# Microcontr_leur_et_capteur_temp.net
KiCad netlist of a schematic drawn in Altium Designer
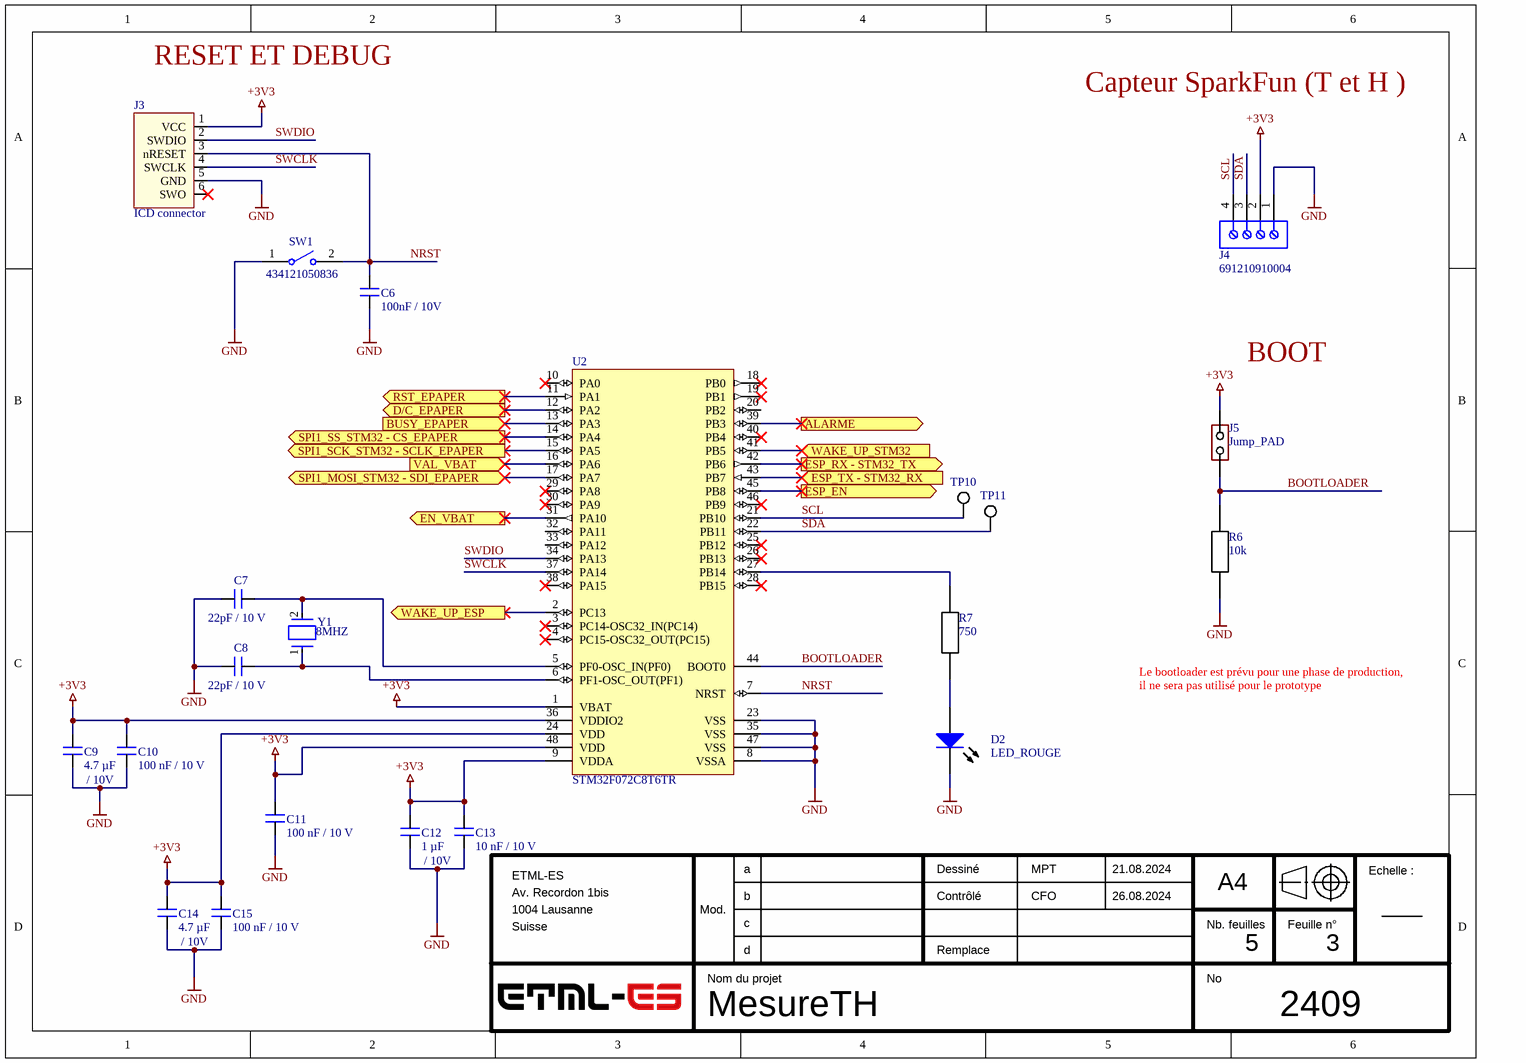
[diagram p0: Microcontrôleur et capteur temp.SchDoc]

(export (version "E")
  (design (tool "Eeschema 10.0.6"))
  (components
    (comp (ref "C6")
      (value "100nF / 10V")
      (footprint "WCAP-CSGP_0805_L2W1.25H0.8_Wave")
      (libsource (lib "Composants_Projet_2409") (part "CAPA"))
    )
    (comp (ref "C7")
      (value "22pF / 10 V")
      (footprint "WCAP-CSGP_0805_L2W1.25H0.8_Wave")
      (libsource (lib "Composants_Projet_2409") (part "CAPA"))
    )
    (comp (ref "C8")
      (value "22pF / 10 V")
      (footprint "WCAP-CSGP_0805_L2W1.25H0.8_Wave")
      (libsource (lib "Composants_Projet_2409") (part "CAPA"))
    )
    (comp (ref "C9")
      (value "4.7 µF")
      (footprint "WCAP-CSGP_0805_L2W1.25H0.8_Wave")
      (libsource (lib "Composants_Projet_2409") (part "CAPA"))
    )
    (comp (ref "C10")
      (value "100 nF / 10 V")
      (footprint "WCAP-CSGP_0805_L2W1.25H0.8_Wave")
      (libsource (lib "Composants_Projet_2409") (part "CAPA"))
    )
    (comp (ref "C11")
      (value "100 nF / 10 V")
      (footprint "WCAP-CSGP_0805_L2W1.25H0.8_Wave")
      (libsource (lib "Composants_Projet_2409") (part "CAPA"))
    )
    (comp (ref "C12")
      (value "1 µF")
      (footprint "WCAP-CSGP_0805_L2W1.25H0.8_Wave")
      (libsource (lib "Composants_Projet_2409") (part "CAPA"))
    )
    (comp (ref "C13")
      (value "10 nF / 10 V")
      (footprint "WCAP-CSGP_0805_L2W1.25H0.8_Wave")
      (libsource (lib "Composants_Projet_2409") (part "CAPA"))
    )
    (comp (ref "C14")
      (value "4.7 µF")
      (footprint "WCAP-CSGP_0805_L2W1.25H0.8_Wave")
      (libsource (lib "Composants_Projet_2409") (part "CAPA"))
    )
    (comp (ref "C15")
      (value "100 nF / 10 V")
      (footprint "WCAP-CSGP_0805_L2W1.25H0.8_Wave")
      (libsource (lib "Composants_Projet_2409") (part "CAPA"))
    )
    (comp (ref "D2")
      (value "LED_ROUGE")
      (footprint "LED_SMD_B_AND_R")
      (libsource (lib "Composants_Projet_2409") (part "LED"))
    )
    (comp (ref "J3")
      (value "ICD connector")
      (footprint "TC2030-MCP")
      (description "Conector par STlinj")
      (libsource (lib "Composants_Projet_2409") (part "TC2030-MCP-NL"))
    )
    (comp (ref "J4")
      (value "691210910004")
      (footprint "691210910004")
      (libsource (lib "Altium Content Vault") (part "TBL - 1R - 04P - Screw"))
    )
    (comp (ref "J5")
      (value "Jump_PAD")
      (footprint "Jump_PAD")
      (description "jump pad smd")
      (libsource (lib "Composants_Projet_2409") (part "Jump_PAD"))
    )
    (comp (ref "R6")
      (value "10k")
      (footprint "WRIS-PSMB_0805_L2W1.25H0.35")
      (libsource (lib "Composants_Projet_2409") (part "Resistance"))
    )
    (comp (ref "R7")
      (value "750")
      (footprint "WRIS-PSMB_0805_L2W1.25H0.35")
      (libsource (lib "Composants_Projet_2409") (part "Resistance"))
    )
    (comp (ref "SW1")
      (value "434121050836")
      (footprint "WS-TASV_L6W3.5H5_4341x10508x6")
      (libsource (lib "Altium Content Vault") (part "SPST-NO_2P"))
    )
    (comp (ref "TP10")
      (value "Test_Point_SMD")
      (footprint "5019")
      (libsource (lib "Composants_Projet_2409") (part "Test_Point_SMD"))
    )
    (comp (ref "TP11")
      (value "Test_Point_SMD")
      (footprint "5019")
      (libsource (lib "Composants_Projet_2409") (part "Test_Point_SMD"))
    )
    (comp (ref "U2")
      (value "STM32F072C8T6TR")
      (footprint "LQFP48-7x7mm")
      (fields (field (name "MANUFACTURER") "STMicroelectronics") (field (name "PARTNUMBER") "STM32F072C8T6"))
      (libsource (lib "Composants_Projet_2409") (part "STM32F072C8T6TR"))
    )
    (comp (ref "Y1")
      (value "8MHZ")
      (footprint "FP-ABLS-MFG")
      (description "CRYSTAL 8.0000MHZ 18PF SMD")
      (fields (field (name "TOLERANCE") "20ppm"))
      (libsource (lib "Altium Content Vault") (part "c23a69dc6c9e2f18f2079038eb95dd1"))
    )
  )
  (nets
    (net (code "1") (name "+3V3") (class "Default")
      (node (ref "C10") (pin "1") (pinfunction "+_1") (pintype "passive"))
      (node (ref "C11") (pin "1") (pinfunction "+_1") (pintype "passive"))
      (node (ref "C12") (pin "1") (pinfunction "+_1") (pintype "passive"))
      (node (ref "C13") (pin "1") (pinfunction "+_1") (pintype "passive"))
      (node (ref "C14") (pin "1") (pinfunction "+_1") (pintype "passive"))
      (node (ref "C15") (pin "1") (pinfunction "+_1") (pintype "passive"))
      (node (ref "C9") (pin "1") (pinfunction "+_1") (pintype "passive"))
      (node (ref "J3") (pin "1") (pinfunction "VCC_1") (pintype "passive"))
      (node (ref "J4") (pin "2") (pinfunction "2_2") (pintype "passive"))
      (node (ref "J5") (pin "2") (pintype "passive"))
      (node (ref "U2") (pin "1") (pinfunction "VBAT_1") (pintype "power_in"))
      (node (ref "U2") (pin "24") (pinfunction "VDD_24") (pintype "power_in"))
      (node (ref "U2") (pin "36") (pinfunction "VDDIO2_36") (pintype "power_in"))
      (node (ref "U2") (pin "48") (pinfunction "VDD_48") (pintype "power_in"))
      (node (ref "U2") (pin "9") (pinfunction "VDDA_9") (pintype "power_in"))
    )
    (net (code "2") (name "/ALARME") (class "Default")
      (node (ref "U2") (pin "39") (pinfunction "PB3_39") (pintype "bidirectional+no_connect"))
    )
    (net (code "3") (name "/BOOTLOADER") (class "Default")
      (node (ref "J5") (pin "1") (pintype "passive"))
      (node (ref "R6") (pin "2") (pinfunction "2_2") (pintype "passive"))
      (node (ref "U2") (pin "44") (pinfunction "BOOT0_44") (pintype "passive"))
    )
    (net (code "4") (name "/BUSY_EPAPER") (class "Default")
      (node (ref "U2") (pin "13") (pinfunction "PA3_13") (pintype "bidirectional+no_connect"))
    )
    (net (code "5") (name "/D{slash}C_EPAPER") (class "Default")
      (node (ref "U2") (pin "12") (pinfunction "PA2_12") (pintype "bidirectional+no_connect"))
    )
    (net (code "6") (name "/EN_VBAT") (class "Default")
      (node (ref "U2") (pin "31") (pinfunction "PA10_31") (pintype "output+no_connect"))
    )
    (net (code "7") (name "/ESP_EN") (class "Default")
      (node (ref "U2") (pin "45") (pinfunction "PB8_45") (pintype "bidirectional+no_connect"))
    )
    (net (code "8") (name "/ESP_RX - STM32_TX") (class "Default")
      (node (ref "U2") (pin "42") (pinfunction "PB6_42") (pintype "output+no_connect"))
    )
    (net (code "9") (name "/ESP_TX - STM32_RX") (class "Default")
      (node (ref "U2") (pin "43") (pinfunction "PB7_43") (pintype "input+no_connect"))
    )
    (net (code "10") (name "/NRST") (class "Default")
      (node (ref "C6") (pin "1") (pinfunction "+_1") (pintype "passive"))
      (node (ref "J3") (pin "3") (pinfunction "nRESET_3") (pintype "passive"))
      (node (ref "SW1") (pin "2") (pinfunction "2_2") (pintype "passive"))
      (node (ref "U2") (pin "7") (pinfunction "NRST_7") (pintype "bidirectional"))
    )
    (net (code "11") (name "/RST_EPAPER") (class "Default")
      (node (ref "U2") (pin "11") (pinfunction "PA1_11") (pintype "input+no_connect"))
    )
    (net (code "12") (name "/SCL") (class "Default")
      (node (ref "J4") (pin "4") (pinfunction "4_4") (pintype "passive"))
      (node (ref "TP10") (pin "1") (pinfunction "1_1") (pintype "passive"))
      (node (ref "U2") (pin "21") (pinfunction "PB10_21") (pintype "bidirectional"))
    )
    (net (code "13") (name "/SDA") (class "Default")
      (node (ref "J4") (pin "3") (pinfunction "3_3") (pintype "passive"))
      (node (ref "TP11") (pin "1") (pinfunction "1_1") (pintype "passive"))
      (node (ref "U2") (pin "22") (pinfunction "PB11_22") (pintype "bidirectional"))
    )
    (net (code "14") (name "/SPI1_MOSI_STM32 - SDI_EPAPER") (class "Default")
      (node (ref "U2") (pin "17") (pinfunction "PA7_17") (pintype "bidirectional+no_connect"))
    )
    (net (code "15") (name "/SPI1_SCK_STM32 - SCLK_EPAPER") (class "Default")
      (node (ref "U2") (pin "15") (pinfunction "PA5_15") (pintype "bidirectional+no_connect"))
    )
    (net (code "16") (name "/SPI1_SS_STM32 - CS_EPAPER") (class "Default")
      (node (ref "U2") (pin "14") (pinfunction "PA4_14") (pintype "bidirectional+no_connect"))
    )
    (net (code "17") (name "/SWCLK") (class "Default")
      (node (ref "J3") (pin "4") (pinfunction "SWCLK_4") (pintype "passive"))
      (node (ref "U2") (pin "37") (pinfunction "PA14_37") (pintype "bidirectional"))
    )
    (net (code "18") (name "/SWDIO") (class "Default")
      (node (ref "J3") (pin "2") (pinfunction "SWDIO_2") (pintype "passive"))
      (node (ref "U2") (pin "34") (pinfunction "PA13_34") (pintype "bidirectional"))
    )
    (net (code "19") (name "/VAL_VBAT") (class "Default")
      (node (ref "U2") (pin "16") (pinfunction "PA6_16") (pintype "bidirectional+no_connect"))
    )
    (net (code "20") (name "/WAKE_UP_ESP") (class "Default")
      (node (ref "U2") (pin "2") (pinfunction "PC13_2") (pintype "bidirectional+no_connect"))
    )
    (net (code "21") (name "/WAKE_UP_STM32") (class "Default")
      (node (ref "U2") (pin "41") (pinfunction "PB5_41") (pintype "bidirectional+no_connect"))
    )
    (net (code "22") (name "GND") (class "Default")
      (node (ref "C10") (pin "2") (pinfunction "-_2") (pintype "passive"))
      (node (ref "C11") (pin "2") (pinfunction "-_2") (pintype "passive"))
      (node (ref "C12") (pin "2") (pinfunction "-_2") (pintype "passive"))
      (node (ref "C13") (pin "2") (pinfunction "-_2") (pintype "passive"))
      (node (ref "C14") (pin "2") (pinfunction "-_2") (pintype "passive"))
      (node (ref "C15") (pin "2") (pinfunction "-_2") (pintype "passive"))
      (node (ref "C6") (pin "2") (pinfunction "-_2") (pintype "passive"))
      (node (ref "C7") (pin "1") (pinfunction "+_1") (pintype "passive"))
      (node (ref "C8") (pin "1") (pinfunction "+_1") (pintype "passive"))
      (node (ref "C9") (pin "2") (pinfunction "-_2") (pintype "passive"))
      (node (ref "D2") (pin "1") (pinfunction "K_1") (pintype "passive"))
      (node (ref "J3") (pin "5") (pinfunction "GND_5") (pintype "passive"))
      (node (ref "J4") (pin "1") (pinfunction "1_1") (pintype "passive"))
      (node (ref "R6") (pin "1") (pinfunction "1_1") (pintype "passive"))
      (node (ref "SW1") (pin "1") (pinfunction "1_1") (pintype "passive"))
      (node (ref "U2") (pin "23") (pinfunction "VSS_23") (pintype "power_in"))
      (node (ref "U2") (pin "35") (pinfunction "VSS_35") (pintype "power_in"))
      (node (ref "U2") (pin "47") (pinfunction "VSS_47") (pintype "power_in"))
      (node (ref "U2") (pin "8") (pinfunction "VSSA_8") (pintype "power_in"))
    )
    (net (code "23") (name "Net-(C7--)") (class "Default")
      (node (ref "C7") (pin "2") (pinfunction "-_2") (pintype "passive"))
      (node (ref "U2") (pin "5") (pinfunction "PF0-OSC_IN(PF0)_5") (pintype "bidirectional"))
      (node (ref "Y1") (pin "2") (pinfunction "2_2") (pintype "passive"))
    )
    (net (code "24") (name "Net-(C8--)") (class "Default")
      (node (ref "C8") (pin "2") (pinfunction "-_2") (pintype "passive"))
      (node (ref "U2") (pin "6") (pinfunction "PF1-OSC_OUT(PF1)_6") (pintype "bidirectional"))
      (node (ref "Y1") (pin "1") (pinfunction "1_1") (pintype "passive"))
    )
    (net (code "25") (name "Net-(D2-A)") (class "Default")
      (node (ref "D2") (pin "2") (pinfunction "A_2") (pintype "passive"))
      (node (ref "R7") (pin "1") (pinfunction "1_1") (pintype "passive"))
    )
    (net (code "26") (name "Net-(U2-PB14)") (class "Default")
      (node (ref "R7") (pin "2") (pinfunction "2_2") (pintype "passive"))
      (node (ref "U2") (pin "27") (pinfunction "PB14_27") (pintype "bidirectional"))
    )
    (net (code "27") (name "unconnected-(J3-SWO-Pad6)") (class "Default")
      (node (ref "J3") (pin "6") (pinfunction "SWO_6") (pintype "passive+no_connect"))
    )
    (net (code "28") (name "unconnected-(U2-PA0-Pad10)") (class "Default")
      (node (ref "U2") (pin "10") (pinfunction "PA0_10") (pintype "bidirectional+no_connect"))
    )
    (net (code "29") (name "unconnected-(U2-PA8-Pad29)") (class "Default")
      (node (ref "U2") (pin "29") (pinfunction "PA8_29") (pintype "bidirectional+no_connect"))
    )
    (net (code "30") (name "unconnected-(U2-PA9-Pad30)") (class "Default")
      (node (ref "U2") (pin "30") (pinfunction "PA9_30") (pintype "bidirectional+no_connect"))
    )
    (net (code "31") (name "unconnected-(U2-PA11-Pad32)") (class "Default")
      (node (ref "U2") (pin "32") (pinfunction "PA11_32") (pintype "bidirectional"))
    )
    (net (code "32") (name "unconnected-(U2-PA12-Pad33)") (class "Default")
      (node (ref "U2") (pin "33") (pinfunction "PA12_33") (pintype "bidirectional"))
    )
    (net (code "33") (name "unconnected-(U2-PA15-Pad38)") (class "Default")
      (node (ref "U2") (pin "38") (pinfunction "PA15_38") (pintype "bidirectional+no_connect"))
    )
    (net (code "34") (name "unconnected-(U2-PB0-Pad18)") (class "Default")
      (node (ref "U2") (pin "18") (pinfunction "PB0_18") (pintype "output+no_connect"))
    )
    (net (code "35") (name "unconnected-(U2-PB1-Pad19)") (class "Default")
      (node (ref "U2") (pin "19") (pinfunction "PB1_19") (pintype "output+no_connect"))
    )
    (net (code "36") (name "unconnected-(U2-PB2-Pad20)") (class "Default")
      (node (ref "U2") (pin "20") (pinfunction "PB2_20") (pintype "bidirectional"))
    )
    (net (code "37") (name "unconnected-(U2-PB4-Pad40)") (class "Default")
      (node (ref "U2") (pin "40") (pinfunction "PB4_40") (pintype "bidirectional+no_connect"))
    )
    (net (code "38") (name "unconnected-(U2-PB9-Pad46)") (class "Default")
      (node (ref "U2") (pin "46") (pinfunction "PB9_46") (pintype "bidirectional+no_connect"))
    )
    (net (code "39") (name "unconnected-(U2-PB12-Pad25)") (class "Default")
      (node (ref "U2") (pin "25") (pinfunction "PB12_25") (pintype "bidirectional+no_connect"))
    )
    (net (code "40") (name "unconnected-(U2-PB13-Pad26)") (class "Default")
      (node (ref "U2") (pin "26") (pinfunction "PB13_26") (pintype "bidirectional+no_connect"))
    )
    (net (code "41") (name "unconnected-(U2-PB15-Pad28)") (class "Default")
      (node (ref "U2") (pin "28") (pinfunction "PB15_28") (pintype "bidirectional+no_connect"))
    )
    (net (code "42") (name "unconnected-(U2-PC14-OSC32_IN(PC14)-Pad3)") (class "Default")
      (node (ref "U2") (pin "3") (pinfunction "PC14-OSC32_IN(PC14)_3") (pintype "bidirectional+no_connect"))
    )
    (net (code "43") (name "unconnected-(U2-PC15-OSC32_OUT(PC15)-Pad4)") (class "Default")
      (node (ref "U2") (pin "4") (pinfunction "PC15-OSC32_OUT(PC15)_4") (pintype "bidirectional+no_connect"))
    )
  )
)
